# MR_UartConnector.net
KiCad netlist of a schematic drawn in Altium Designer
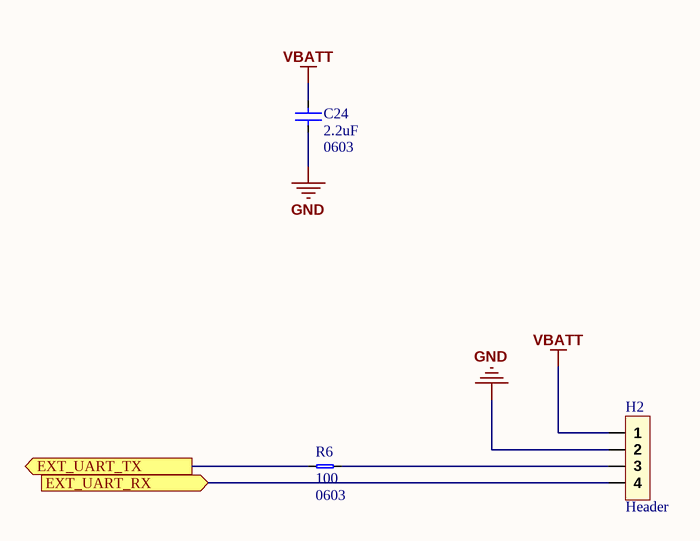
[diagram p0: MR_UartConnector.SchDoc]

(export (version "E")
  (design (tool "Eeschema 10.0.6"))
  (components
    (comp (ref "C24")
      (value "2.2uF")
      (footprint "0603_CAP_LD")
      (description "Ceramic Capacitor")
      (fields (field (name "PACKAGE") "0603") (field (name "Comment") "CerCap"))
      (libsource (lib "MiniRobot") (part "CerCap"))
    )
    (comp (ref "H2")
      (value "Header")
      (footprint "HE14 1x4 Straight")
      (description "Header 4x1 PIns")
      (libsource (lib "MiniRobot") (part "Header_4x1"))
    )
    (comp (ref "R6")
      (value "100")
      (footprint "0603_RES_LD")
      (description "Resistor")
      (fields (field (name "PACKAGE") "0603"))
      (libsource (lib "MiniRobot") (part "Resistor"))
    )
  )
  (nets
    (net (code "1") (name "/EXT_UART_RX") (class "Default")
      (node (ref "H2") (pin "4") (pinfunction "4_4") (pintype "passive"))
    )
    (net (code "2") (name "/EXT_UART_TX") (class "Default")
      (node (ref "R6") (pin "1") (pinfunction "1_1") (pintype "passive"))
    )
    (net (code "3") (name "GND") (class "Default")
      (node (ref "C24") (pin "1") (pinfunction "1_1") (pintype "passive"))
      (node (ref "H2") (pin "2") (pinfunction "2_2") (pintype "passive"))
    )
    (net (code "4") (name "Net-(H2-Pad3)") (class "Default")
      (node (ref "H2") (pin "3") (pinfunction "3_3") (pintype "passive"))
      (node (ref "R6") (pin "2") (pinfunction "2_2") (pintype "passive"))
    )
    (net (code "5") (name "VBATT") (class "Default")
      (node (ref "C24") (pin "2") (pinfunction "2_2") (pintype "passive"))
      (node (ref "H2") (pin "1") (pinfunction "1_1") (pintype "passive"))
    )
  )
)
